# Omvorming.net
KiCad netlist of a schematic drawn in Altium Designer
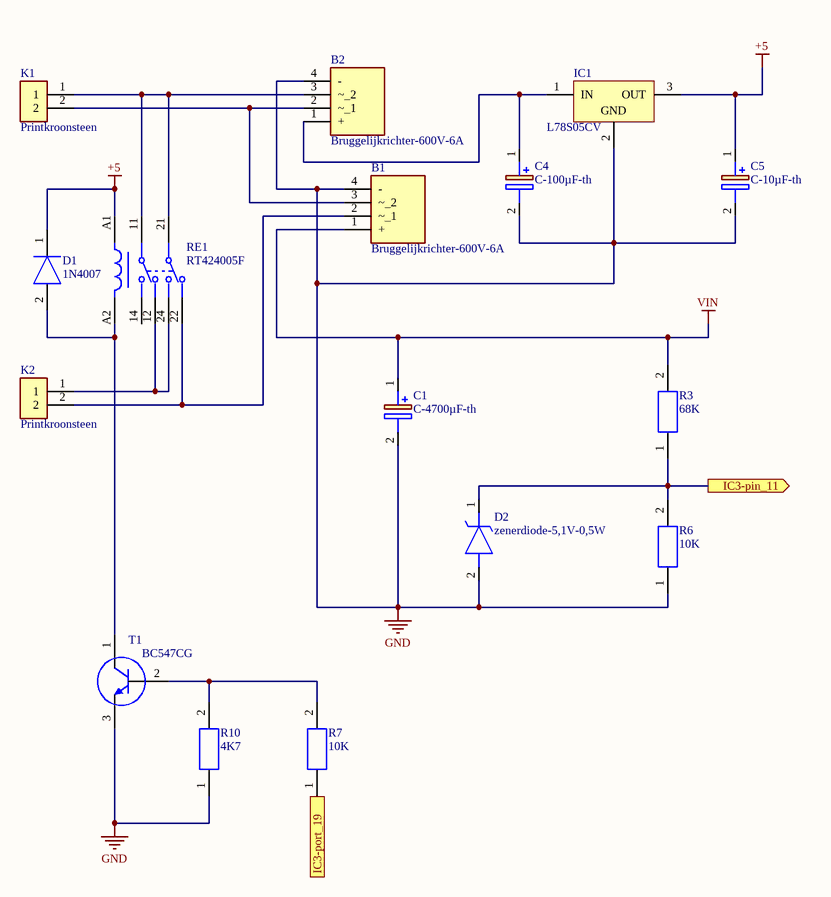
[diagram p0: Omvorming.SchDoc]

(export (version "E")
  (design (tool "Eeschema 10.0.6"))
  (components
    (comp (ref "B1")
      (value "Bruggelijkrichter-600V-6A")
      (footprint "Bruggelijkrichter-600V-6A")
      (description "Bridge Rectifier")
      (fields (field (name "MANUFACTURER_PART_NUMBER") "GBU6J-E3/45"))
      (libsource (lib "project-2022") (part "Bruggelijkrichter-600V-6A"))
    )
    (comp (ref "B2")
      (value "Bruggelijkrichter-600V-6A")
      (footprint "Bruggelijkrichter-600V-6A")
      (description "Bridge Rectifier")
      (fields (field (name "MANUFACTURER_PART_NUMBER") "GBU6J-E3/45"))
      (libsource (lib "project-2022") (part "Bruggelijkrichter-600V-6A"))
    )
    (comp (ref "C1")
      (value "C-4700µF-th")
      (footprint "C-4700µF-th")
      (description "Capacitor Polarised")
      (fields
        (field (name "MOUSER2 PART NUMBER") "80-ESK478M050AQ3AA")
        (field (name "MANUFACTURER_PART_NUMBER") "ESK478M050AQ3AA")
      )
      (libsource (lib "project-2022") (part "C-4700µF-th"))
    )
    (comp (ref "C4")
      (value "C-100µF-th")
      (footprint "C-100µF-th")
      (description "Capacitor Polarised")
      (fields (field (name "MANUFACTURER_PART_NUMBER") "ESK107M050AG3EA"))
      (libsource (lib "project-2022") (part "C-100µF-th"))
    )
    (comp (ref "C5")
      (value "C-10µF-th")
      (footprint "C-10µF-th")
      (description "Capacitor Polarised")
      (fields
        (field (name "MOUSER2 PART NUMBER") "667-ECA-1HM100I")
        (field (name "MANUFACTURER_PART_NUMBER") "ECA-1HM100I")
      )
      (libsource (lib "project-2022") (part "C-10µF-th"))
    )
    (comp (ref "D1")
      (value "1N4007")
      (footprint "1N4007")
      (description "Diode")
      (fields
        (field (name "MOUSER2 PART NUMBER") "583-1N4007-T")
        (field (name "MANUFACTURER_PART_NUMBER") "1N4007-T")
      )
      (libsource (lib "project-2022") (part "1N4007"))
    )
    (comp (ref "D2")
      (value "zenerdiode-5,1V-0,5W")
      (footprint "zenerdiode-5,1V-0,5W")
      (description "Zener Diode")
      (fields (field (name "MANUFACTURER_PART_NUMBER") "MM5Z4689T1G"))
      (libsource (lib "project-2022") (part "zenerdiode-5,1V-0,5W"))
    )
    (comp (ref "IC1")
      (value "L78S05CV")
      (footprint "5V_Regulator-2A")
      (description "2A Positive Voltage Regulator, 5V, 3-Pin TO-220")
      (libsource (lib "project-2022") (part "5V_Regulator-2A"))
    )
    (comp (ref "K1")
      (value "Printkroonsteen")
      (footprint "Printkroonsteen")
      (description "Connector")
      (fields
        (field (name "MOUSER2 PART NUMBER") "490-TB007-508-02BE")
        (field (name "MANUFACTURER_PART_NUMBER") "TB007-508-02BE")
      )
      (libsource (lib "project-2022") (part "Printkroonsteen"))
    )
    (comp (ref "K2")
      (value "Printkroonsteen")
      (footprint "Printkroonsteen")
      (description "Connector")
      (fields
        (field (name "MOUSER2 PART NUMBER") "490-TB007-508-02BE")
        (field (name "MANUFACTURER_PART_NUMBER") "TB007-508-02BE")
      )
      (libsource (lib "project-2022") (part "Printkroonsteen"))
    )
    (comp (ref "R3")
      (value "68K")
      (footprint "R-0805")
      (description "Resistor")
      (fields (field (name "MANUFACTURER_PART_NUMBER") "TNPU0805500RAZEN00"))
      (libsource (lib "project-2022") (part "R-0805"))
    )
    (comp (ref "R6")
      (value "10K")
      (footprint "R-0805")
      (description "Resistor")
      (fields (field (name "MANUFACTURER_PART_NUMBER") "TNPU0805500RAZEN00"))
      (libsource (lib "project-2022") (part "R-0805"))
    )
    (comp (ref "R7")
      (value "10K")
      (footprint "R-0805")
      (description "Resistor")
      (fields (field (name "MANUFACTURER_PART_NUMBER") "TNPU0805500RAZEN00"))
      (libsource (lib "project-2022") (part "R-0805"))
    )
    (comp (ref "R10")
      (value "4K7")
      (footprint "R-0805")
      (description "Resistor")
      (fields (field (name "MANUFACTURER_PART_NUMBER") "TNPU0805500RAZEN00"))
      (libsource (lib "project-2022") (part "R-0805"))
    )
    (comp (ref "RE1")
      (value "RT424005F")
      (footprint "vermogenrelais-5VDC-8A")
      (description "RELAY GENERAL PURPOSE DPDT 8A 5V")
      (libsource (lib "project-2022") (part "vermogenrelais-5VDC-8A"))
    )
    (comp (ref "T1")
      (value "BC547CG")
      (footprint "BC547C")
      (description "Amplifier Transistor, NPN Silicon, 3-Pin TO-92, Pb-Free, Bulk Box")
      (fields (field (name "MANUFACTURER") "On Semiconductor"))
      (libsource (lib "project-2022") (part "BC547C"))
    )
  )
  (nets
    (net (code "1") (name "+5") (class "Default")
      (node (ref "C5") (pin "1") (pinfunction "+_1") (pintype "passive"))
      (node (ref "D1") (pin "1") (pinfunction "K_1") (pintype "passive"))
      (node (ref "IC1") (pin "3") (pinfunction "OUT_3") (pintype "power_in"))
      (node (ref "RE1") (pin "A1") (pinfunction "A1_A1") (pintype "passive"))
    )
    (net (code "2") (name "/IC3-pin_11") (class "Default")
      (node (ref "D2") (pin "1") (pinfunction "K_1") (pintype "passive"))
      (node (ref "R3") (pin "1") (pinfunction "1_1") (pintype "passive"))
      (node (ref "R6") (pin "2") (pinfunction "2_2") (pintype "passive"))
    )
    (net (code "3") (name "/IC3-port_19") (class "Default")
      (node (ref "R7") (pin "1") (pinfunction "1_1") (pintype "passive"))
    )
    (net (code "4") (name "GND") (class "Default")
      (node (ref "B1") (pin "4") (pinfunction "-_4") (pintype "passive"))
      (node (ref "B2") (pin "4") (pinfunction "-_4") (pintype "passive"))
      (node (ref "C1") (pin "2") (pinfunction "-_2") (pintype "passive"))
      (node (ref "C4") (pin "2") (pinfunction "-_2") (pintype "passive"))
      (node (ref "C5") (pin "2") (pinfunction "-_2") (pintype "passive"))
      (node (ref "D2") (pin "2") (pinfunction "A_2") (pintype "passive"))
      (node (ref "IC1") (pin "2") (pinfunction "GND_2") (pintype "power_in"))
      (node (ref "R10") (pin "1") (pinfunction "1_1") (pintype "passive"))
      (node (ref "R6") (pin "1") (pinfunction "1_1") (pintype "passive"))
      (node (ref "T1") (pin "3") (pinfunction "E_3") (pintype "passive"))
    )
    (net (code "5") (name "Net-(B1-~_1)") (class "Default")
      (node (ref "B1") (pin "2") (pinfunction "~_1_2") (pintype "passive"))
      (node (ref "K2") (pin "2") (pinfunction "2_2") (pintype "passive"))
      (node (ref "RE1") (pin "22") (pinfunction "22_22") (pintype "passive"))
    )
    (net (code "6") (name "Net-(B1-~_2)") (class "Default")
      (node (ref "B1") (pin "3") (pinfunction "~_2_3") (pintype "passive"))
      (node (ref "B2") (pin "2") (pinfunction "~_1_2") (pintype "passive"))
      (node (ref "K1") (pin "2") (pinfunction "2_2") (pintype "passive"))
    )
    (net (code "7") (name "Net-(B2-+)") (class "Default")
      (node (ref "B2") (pin "1") (pinfunction "+_1") (pintype "passive"))
      (node (ref "C4") (pin "1") (pinfunction "+_1") (pintype "passive"))
      (node (ref "IC1") (pin "1") (pinfunction "IN_1") (pintype "power_in"))
    )
    (net (code "8") (name "Net-(B2-~_2)") (class "Default")
      (node (ref "B2") (pin "3") (pinfunction "~_2_3") (pintype "passive"))
      (node (ref "K1") (pin "1") (pinfunction "1_1") (pintype "passive"))
      (node (ref "RE1") (pin "11") (pinfunction "11_11") (pintype "passive"))
      (node (ref "RE1") (pin "21") (pinfunction "21_21") (pintype "passive"))
    )
    (net (code "9") (name "Net-(D1-A)") (class "Default")
      (node (ref "D1") (pin "2") (pinfunction "A_2") (pintype "passive"))
      (node (ref "RE1") (pin "A2") (pinfunction "A2_A2") (pintype "passive"))
      (node (ref "T1") (pin "1") (pinfunction "C_1") (pintype "passive"))
    )
    (net (code "10") (name "Net-(K2-Pad1)") (class "Default")
      (node (ref "K2") (pin "1") (pinfunction "1_1") (pintype "passive"))
      (node (ref "RE1") (pin "12") (pinfunction "12_12") (pintype "passive"))
      (node (ref "RE1") (pin "24") (pinfunction "24_24") (pintype "passive"))
    )
    (net (code "11") (name "Net-(T1-B)") (class "Default")
      (node (ref "R10") (pin "2") (pinfunction "2_2") (pintype "passive"))
      (node (ref "R7") (pin "2") (pinfunction "2_2") (pintype "passive"))
      (node (ref "T1") (pin "2") (pinfunction "B_2") (pintype "passive"))
    )
    (net (code "12") (name "VIN") (class "Default")
      (node (ref "B1") (pin "1") (pinfunction "+_1") (pintype "passive"))
      (node (ref "C1") (pin "1") (pinfunction "+_1") (pintype "passive"))
      (node (ref "R3") (pin "2") (pinfunction "2_2") (pintype "passive"))
    )
    (net (code "13") (name "unconnected-(RE1-Pad14)") (class "Default")
      (node (ref "RE1") (pin "14") (pinfunction "14_14") (pintype "passive"))
    )
  )
)
